# LAN_WIZ_V0_1.net
KiCad netlist of a schematic drawn in EAGLE
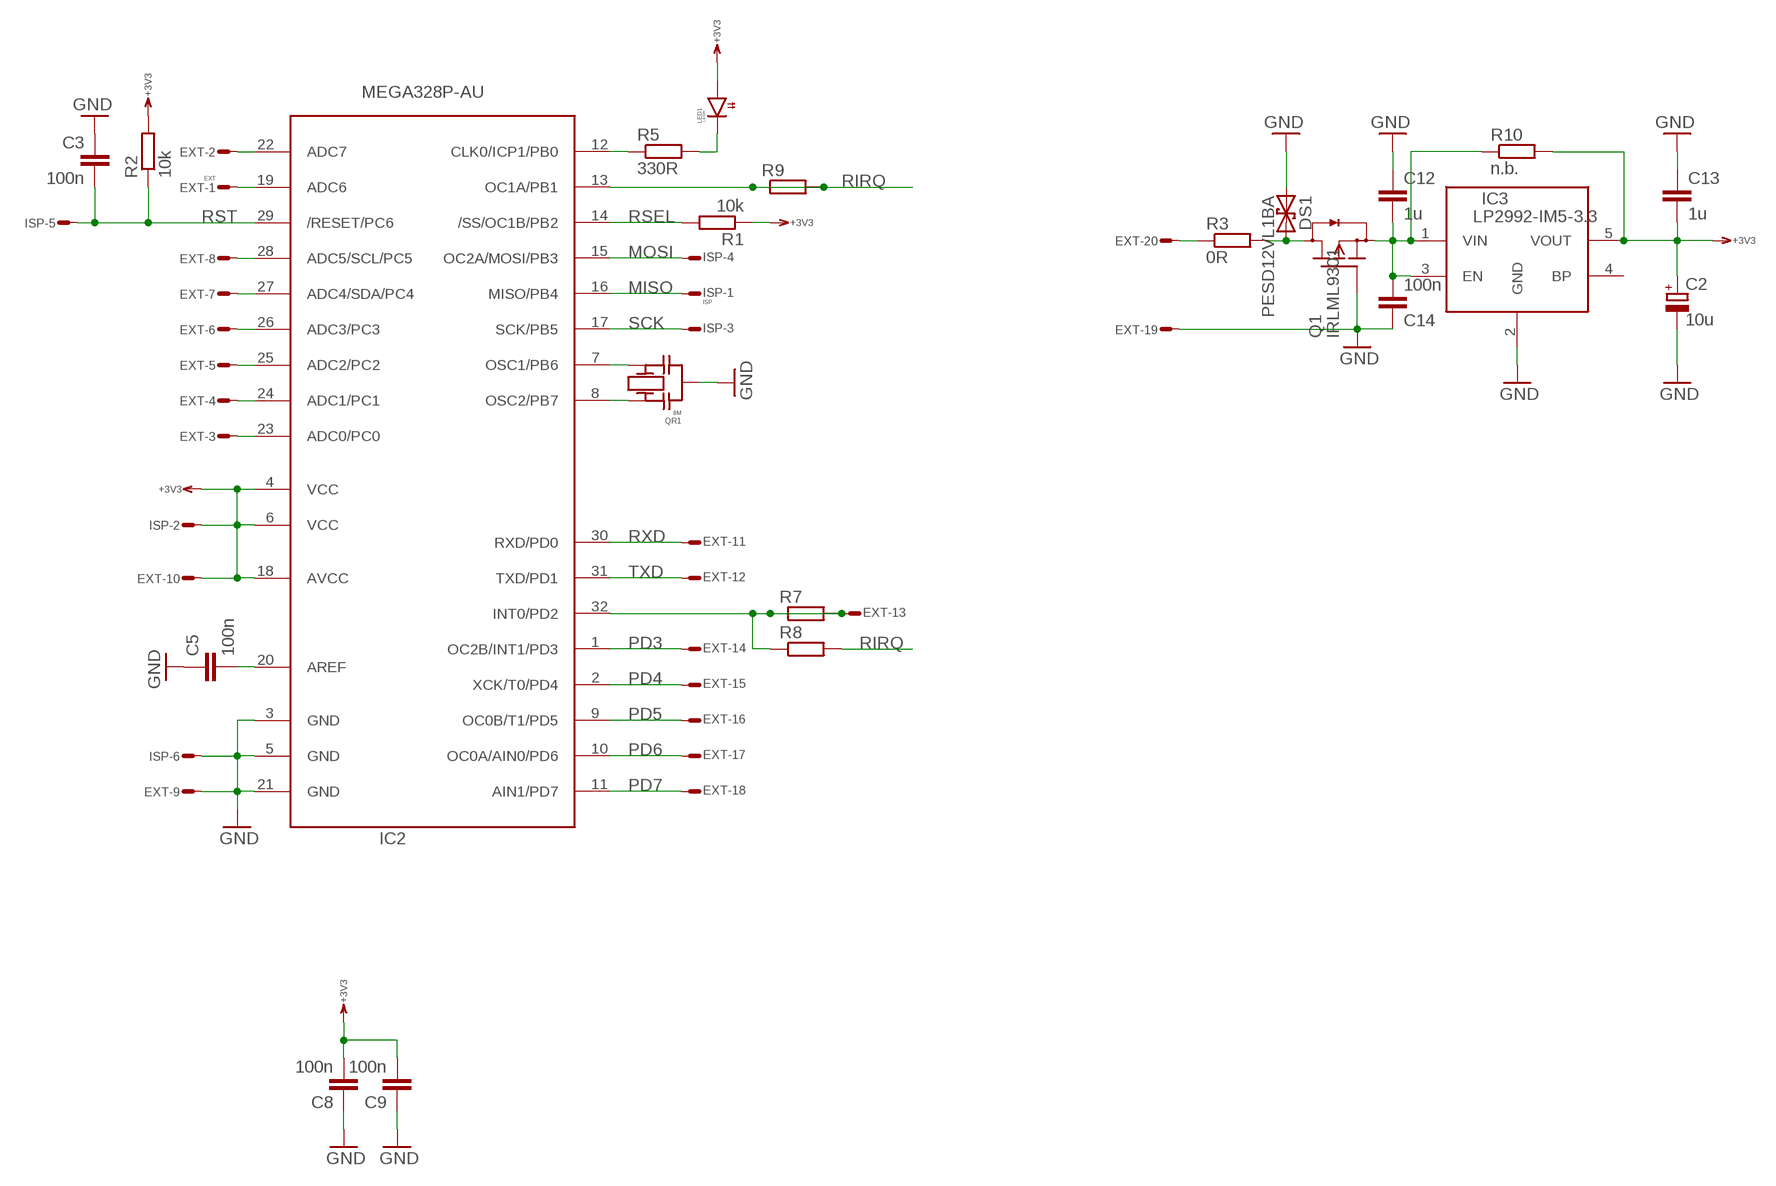
[diagram p0: schematic, sheet 1]

(export (version "E")
  (design (tool "Eeschema 10.0.6"))
  (components
    (comp (ref "C2")
      (value "10u")
      (footprint "eagle-import:SMC_B")
      (libsource (lib "eagle-import") (part "C_POLSMCB"))
    )
    (comp (ref "C3")
      (value "100n")
      (footprint "eagle-import:0603")
      (libsource (lib "eagle-import") (part "C0603"))
    )
    (comp (ref "C5")
      (value "100n")
      (footprint "eagle-import:0603")
      (libsource (lib "eagle-import") (part "C0603"))
    )
    (comp (ref "C8")
      (value "100n")
      (footprint "eagle-import:0603")
      (libsource (lib "eagle-import") (part "C0603"))
    )
    (comp (ref "C9")
      (value "100n")
      (footprint "eagle-import:0603")
      (libsource (lib "eagle-import") (part "C0603"))
    )
    (comp (ref "C12")
      (value "1u")
      (footprint "eagle-import:0603")
      (libsource (lib "eagle-import") (part "C0603"))
    )
    (comp (ref "C13")
      (value "1u")
      (footprint "eagle-import:0603")
      (libsource (lib "eagle-import") (part "C0603"))
    )
    (comp (ref "C14")
      (value "100n")
      (footprint "eagle-import:0603")
      (libsource (lib "eagle-import") (part "C0603"))
    )
    (comp (ref "DS1")
      (value "PESD12VL1BA")
      (footprint "eagle-import:SOD323")
      (libsource (lib "eagle-import") (part "TVS-U323"))
    )
    (comp (ref "EXT")
      (value "EXT")
      (footprint "eagle-import:ML20S")
      (libsource (lib "eagle-import") (part "ML20?ES"))
    )
    (comp (ref "IC2")
      (value "MEGA328P-AU")
      (footprint "eagle-import:TQFP32-08")
      (libsource (lib "eagle-import") (part "MEGA168PA"))
    )
    (comp (ref "IC3")
      (value "LP2992-IM5-3.3")
      (footprint "eagle-import:SOT23-5")
      (libsource (lib "eagle-import") (part "LDO"))
    )
    (comp (ref "ISP")
      (value "ISP")
      (footprint "eagle-import:ML6S")
      (libsource (lib "eagle-import") (part "ML6ES"))
    )
    (comp (ref "LED1")
      (value "LEDR")
      (footprint "eagle-import:0805")
      (libsource (lib "eagle-import") (part "LED0805"))
    )
    (comp (ref "Q1")
      (value "IRLML9301")
      (footprint "eagle-import:SOT23")
      (libsource (lib "eagle-import") (part "FET-PDSOT23"))
    )
    (comp (ref "QR1")
      (value "8M")
      (footprint "eagle-import:CR")
      (libsource (lib "eagle-import") (part "QRCR"))
    )
    (comp (ref "R1")
      (value "10k")
      (footprint "eagle-import:0402")
      (libsource (lib "eagle-import") (part "R0402"))
    )
    (comp (ref "R2")
      (value "10k")
      (footprint "eagle-import:0603")
      (libsource (lib "eagle-import") (part "R0603"))
    )
    (comp (ref "R3")
      (value "0R")
      (footprint "eagle-import:0603")
      (libsource (lib "eagle-import") (part "R0603"))
    )
    (comp (ref "R5")
      (value "330R")
      (footprint "eagle-import:0603")
      (libsource (lib "eagle-import") (part "R0603"))
    )
    (comp (ref "R7")
      (value "R0402")
      (footprint "eagle-import:0402")
      (libsource (lib "eagle-import") (part "R0402"))
    )
    (comp (ref "R8")
      (value "R0402")
      (footprint "eagle-import:0402")
      (libsource (lib "eagle-import") (part "R0402"))
    )
    (comp (ref "R9")
      (value "R0402")
      (footprint "eagle-import:0402")
      (libsource (lib "eagle-import") (part "R0402"))
    )
    (comp (ref "R10")
      (value "n.b.")
      (footprint "eagle-import:0805")
      (libsource (lib "eagle-import") (part "R0805"))
    )
  )
  (nets
    (net (code "1") (name "+3V3") (class "Default")
      (node (ref "C13") (pin "2") (pinfunction "2_2") (pintype "passive"))
      (node (ref "C2") (pin "+") (pinfunction "+_+") (pintype "passive"))
      (node (ref "C8") (pin "2") (pinfunction "2_2") (pintype "passive"))
      (node (ref "C9") (pin "2") (pinfunction "2_2") (pintype "passive"))
      (node (ref "EXT") (pin "10") (pinfunction "S_10") (pintype "passive"))
      (node (ref "IC2") (pin "18") (pinfunction "AVCC_18") (pintype "bidirectional"))
      (node (ref "IC2") (pin "4") (pinfunction "VCC_4") (pintype "bidirectional"))
      (node (ref "IC2") (pin "6") (pinfunction "VCC_6") (pintype "bidirectional"))
      (node (ref "IC3") (pin "5") (pinfunction "VOUT_5") (pintype "bidirectional"))
      (node (ref "ISP") (pin "2") (pinfunction "S_2") (pintype "passive"))
      (node (ref "LED1") (pin "C") (pinfunction "A_C") (pintype "bidirectional"))
      (node (ref "R1") (pin "1") (pinfunction "1_1") (pintype "passive"))
      (node (ref "R10") (pin "2") (pinfunction "2_2") (pintype "passive"))
      (node (ref "R2") (pin "2") (pinfunction "2_2") (pintype "passive"))
    )
    (net (code "2") (name "/MISO") (class "Default")
      (node (ref "IC2") (pin "16") (pinfunction "MISO/PB4_16") (pintype "bidirectional"))
      (node (ref "ISP") (pin "1") (pinfunction "S_1") (pintype "passive"))
    )
    (net (code "3") (name "/MOSI") (class "Default")
      (node (ref "IC2") (pin "15") (pinfunction "OC2A/MOSI/PB3_15") (pintype "bidirectional"))
      (node (ref "ISP") (pin "4") (pinfunction "S_4") (pintype "passive"))
    )
    (net (code "4") (name "/PD3") (class "Default")
      (node (ref "EXT") (pin "14") (pinfunction "S_14") (pintype "passive"))
      (node (ref "IC2") (pin "1") (pinfunction "OC2B/INT1/PD3_1") (pintype "bidirectional"))
    )
    (net (code "5") (name "/PD4") (class "Default")
      (node (ref "EXT") (pin "15") (pinfunction "S_15") (pintype "passive"))
      (node (ref "IC2") (pin "2") (pinfunction "XCK/T0/PD4_2") (pintype "bidirectional"))
    )
    (net (code "6") (name "/PD5") (class "Default")
      (node (ref "EXT") (pin "16") (pinfunction "S_16") (pintype "passive"))
      (node (ref "IC2") (pin "9") (pinfunction "OC0B/T1/PD5_9") (pintype "bidirectional"))
    )
    (net (code "7") (name "/PD6") (class "Default")
      (node (ref "EXT") (pin "17") (pinfunction "S_17") (pintype "passive"))
      (node (ref "IC2") (pin "10") (pinfunction "OC0A/AIN0/PD6_10") (pintype "bidirectional"))
    )
    (net (code "8") (name "/PD7") (class "Default")
      (node (ref "EXT") (pin "18") (pinfunction "S_18") (pintype "passive"))
      (node (ref "IC2") (pin "11") (pinfunction "AIN1/PD7_11") (pintype "bidirectional"))
    )
    (net (code "9") (name "/RIRQ") (class "Default")
      (node (ref "IC2") (pin "13") (pinfunction "OC1A/PB1_13") (pintype "bidirectional"))
      (node (ref "R8") (pin "2") (pinfunction "2_2") (pintype "passive"))
      (node (ref "R9") (pin "1") (pinfunction "1_1") (pintype "passive"))
      (node (ref "R9") (pin "2") (pinfunction "2_2") (pintype "passive"))
    )
    (net (code "10") (name "/RSEL") (class "Default")
      (node (ref "IC2") (pin "14") (pinfunction "/SS/OC1B/PB2_14") (pintype "bidirectional"))
      (node (ref "R1") (pin "2") (pinfunction "2_2") (pintype "passive"))
    )
    (net (code "11") (name "/RST") (class "Default")
      (node (ref "C3") (pin "2") (pinfunction "2_2") (pintype "passive"))
      (node (ref "IC2") (pin "29") (pinfunction "/RESET/PC6_29") (pintype "bidirectional"))
      (node (ref "ISP") (pin "5") (pinfunction "S_5") (pintype "passive"))
      (node (ref "R2") (pin "1") (pinfunction "1_1") (pintype "passive"))
    )
    (net (code "12") (name "/RXD") (class "Default")
      (node (ref "EXT") (pin "11") (pinfunction "S_11") (pintype "passive"))
      (node (ref "IC2") (pin "30") (pinfunction "RXD/PD0_30") (pintype "bidirectional"))
    )
    (net (code "13") (name "/SCK") (class "Default")
      (node (ref "IC2") (pin "17") (pinfunction "SCK/PB5_17") (pintype "bidirectional"))
      (node (ref "ISP") (pin "3") (pinfunction "S_3") (pintype "passive"))
    )
    (net (code "14") (name "/TXD") (class "Default")
      (node (ref "EXT") (pin "12") (pinfunction "S_12") (pintype "passive"))
      (node (ref "IC2") (pin "31") (pinfunction "TXD/PD1_31") (pintype "bidirectional"))
    )
    (net (code "15") (name "GND") (class "Default")
      (node (ref "C12") (pin "1") (pinfunction "1_1") (pintype "passive"))
      (node (ref "C13") (pin "1") (pinfunction "1_1") (pintype "passive"))
      (node (ref "C14") (pin "1") (pinfunction "1_1") (pintype "passive"))
      (node (ref "C2") (pin "-") (pinfunction "-_-") (pintype "passive"))
      (node (ref "C3") (pin "1") (pinfunction "1_1") (pintype "passive"))
      (node (ref "C5") (pin "1") (pinfunction "1_1") (pintype "passive"))
      (node (ref "C8") (pin "1") (pinfunction "1_1") (pintype "passive"))
      (node (ref "C9") (pin "1") (pinfunction "1_1") (pintype "passive"))
      (node (ref "DS1") (pin "A") (pinfunction "1_A") (pintype "passive"))
      (node (ref "EXT") (pin "19") (pinfunction "S_19") (pintype "passive"))
      (node (ref "EXT") (pin "9") (pinfunction "S_9") (pintype "passive"))
      (node (ref "IC2") (pin "21") (pinfunction "GND_21") (pintype "bidirectional"))
      (node (ref "IC2") (pin "3") (pinfunction "GND_3") (pintype "bidirectional"))
      (node (ref "IC2") (pin "5") (pinfunction "GND_5") (pintype "bidirectional"))
      (node (ref "IC3") (pin "2") (pinfunction "GND_2") (pintype "bidirectional"))
      (node (ref "ISP") (pin "6") (pinfunction "S_6") (pintype "passive"))
      (node (ref "Q1") (pin "1") (pinfunction "G_1") (pintype "passive"))
      (node (ref "QR1") (pin "M") (pinfunction "M_M") (pintype "passive"))
    )
    (net (code "16") (name "Net-(DS1-2)") (class "Default")
      (node (ref "DS1") (pin "C") (pinfunction "2_C") (pintype "passive"))
      (node (ref "Q1") (pin "3") (pinfunction "D_3") (pintype "passive"))
      (node (ref "R3") (pin "2") (pinfunction "2_2") (pintype "passive"))
    )
    (net (code "17") (name "Net-(EXTA-S)") (class "Default")
      (node (ref "EXT") (pin "1") (pinfunction "S_1") (pintype "passive"))
      (node (ref "IC2") (pin "19") (pinfunction "ADC6_19") (pintype "bidirectional"))
    )
    (net (code "18") (name "Net-(EXTE-S)") (class "Default")
      (node (ref "EXT") (pin "13") (pinfunction "S_13") (pintype "passive"))
      (node (ref "IC2") (pin "32") (pinfunction "INT0/PD2_32") (pintype "bidirectional"))
      (node (ref "R7") (pin "1") (pinfunction "1_1") (pintype "passive"))
      (node (ref "R7") (pin "2") (pinfunction "2_2") (pintype "passive"))
      (node (ref "R8") (pin "1") (pinfunction "1_1") (pintype "passive"))
    )
    (net (code "19") (name "Net-(EXTL-S)") (class "Default")
      (node (ref "EXT") (pin "2") (pinfunction "S_2") (pintype "passive"))
      (node (ref "IC2") (pin "22") (pinfunction "ADC7_22") (pintype "bidirectional"))
    )
    (net (code "20") (name "Net-(EXTM-S)") (class "Default")
      (node (ref "EXT") (pin "20") (pinfunction "S_20") (pintype "passive"))
      (node (ref "R3") (pin "1") (pinfunction "1_1") (pintype "passive"))
    )
    (net (code "21") (name "Net-(EXTN-S)") (class "Default")
      (node (ref "EXT") (pin "3") (pinfunction "S_3") (pintype "passive"))
      (node (ref "IC2") (pin "23") (pinfunction "ADC0/PC0_23") (pintype "bidirectional"))
    )
    (net (code "22") (name "Net-(EXTO-S)") (class "Default")
      (node (ref "EXT") (pin "4") (pinfunction "S_4") (pintype "passive"))
      (node (ref "IC2") (pin "24") (pinfunction "ADC1/PC1_24") (pintype "bidirectional"))
    )
    (net (code "23") (name "Net-(EXTP-S)") (class "Default")
      (node (ref "EXT") (pin "5") (pinfunction "S_5") (pintype "passive"))
      (node (ref "IC2") (pin "25") (pinfunction "ADC2/PC2_25") (pintype "bidirectional"))
    )
    (net (code "24") (name "Net-(EXTQ-S)") (class "Default")
      (node (ref "EXT") (pin "6") (pinfunction "S_6") (pintype "passive"))
      (node (ref "IC2") (pin "26") (pinfunction "ADC3/PC3_26") (pintype "bidirectional"))
    )
    (net (code "25") (name "Net-(EXTR-S)") (class "Default")
      (node (ref "EXT") (pin "7") (pinfunction "S_7") (pintype "passive"))
      (node (ref "IC2") (pin "27") (pinfunction "ADC4/SDA/PC4_27") (pintype "bidirectional"))
    )
    (net (code "26") (name "Net-(EXTS-S)") (class "Default")
      (node (ref "EXT") (pin "8") (pinfunction "S_8") (pintype "passive"))
      (node (ref "IC2") (pin "28") (pinfunction "ADC5/SCL/PC5_28") (pintype "bidirectional"))
    )
    (net (code "27") (name "Net-(IC2-AREF)") (class "Default")
      (node (ref "C5") (pin "2") (pinfunction "2_2") (pintype "passive"))
      (node (ref "IC2") (pin "20") (pinfunction "AREF_20") (pintype "bidirectional"))
    )
    (net (code "28") (name "Net-(IC2-CLK0{slash}ICP1{slash}PB0)") (class "Default")
      (node (ref "IC2") (pin "12") (pinfunction "CLK0/ICP1/PB0_12") (pintype "bidirectional"))
      (node (ref "R5") (pin "1") (pinfunction "1_1") (pintype "passive"))
    )
    (net (code "29") (name "Net-(IC2-OSC1{slash}PB6)") (class "Default")
      (node (ref "IC2") (pin "7") (pinfunction "OSC1/PB6_7") (pintype "bidirectional"))
      (node (ref "QR1") (pin "2") (pinfunction "2_2") (pintype "passive"))
    )
    (net (code "30") (name "Net-(IC2-OSC2{slash}PB7)") (class "Default")
      (node (ref "IC2") (pin "8") (pinfunction "OSC2/PB7_8") (pintype "bidirectional"))
      (node (ref "QR1") (pin "1") (pinfunction "1_1") (pintype "passive"))
    )
    (net (code "31") (name "Net-(IC3-EN)") (class "Default")
      (node (ref "C12") (pin "2") (pinfunction "2_2") (pintype "passive"))
      (node (ref "C14") (pin "2") (pinfunction "2_2") (pintype "passive"))
      (node (ref "IC3") (pin "1") (pinfunction "VIN_1") (pintype "bidirectional"))
      (node (ref "IC3") (pin "3") (pinfunction "EN_3") (pintype "bidirectional"))
      (node (ref "Q1") (pin "2") (pinfunction "S_2") (pintype "passive"))
      (node (ref "R10") (pin "1") (pinfunction "1_1") (pintype "passive"))
    )
    (net (code "32") (name "Net-(LED1-C)") (class "Default")
      (node (ref "LED1") (pin "A") (pinfunction "C_A") (pintype "bidirectional"))
      (node (ref "R5") (pin "2") (pinfunction "2_2") (pintype "passive"))
    )
    (net (code "33") (name "unconnected-(IC3-BP-Pad4)") (class "Default")
      (node (ref "IC3") (pin "4") (pinfunction "BP_4") (pintype "bidirectional"))
    )
  )
)
